# IODevices.net
KiCad netlist of a schematic drawn in Altium Designer
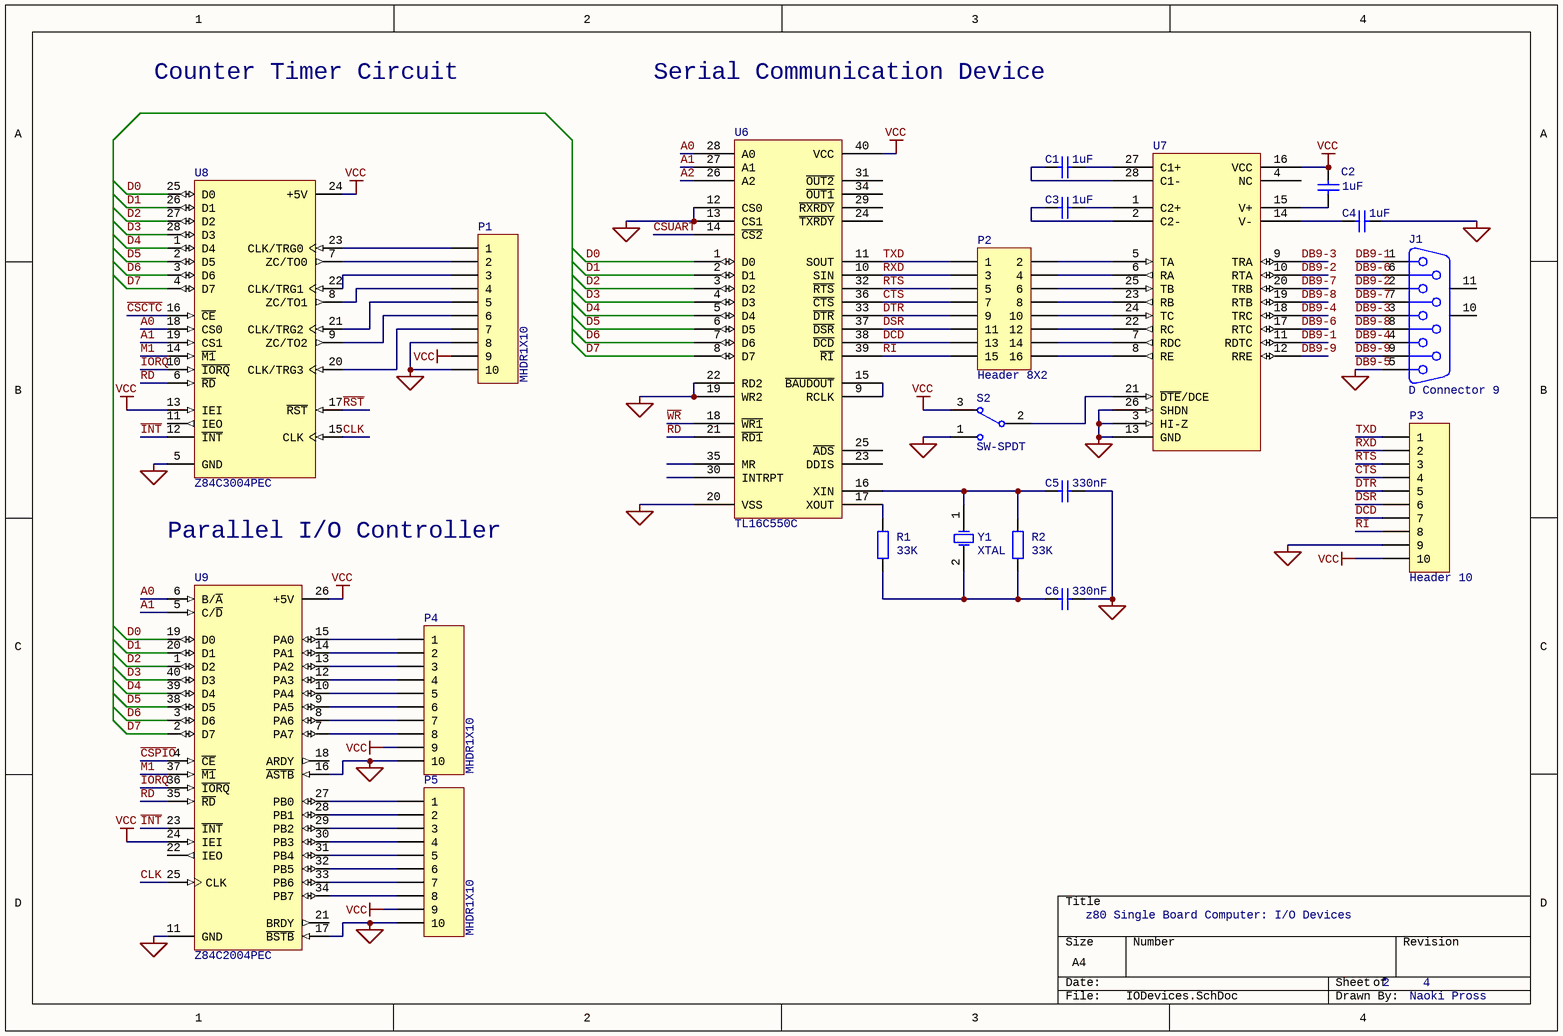
[diagram p0: IODevices.SchDoc]

(export (version "E")
  (design (tool "Eeschema 10.0.6"))
  (components
    (comp (ref "C1")
      (value "1uF")
      (footprint "RAD-0.3")
      (description "Capacitor")
      (fields (field (name "Comment") "Cap") (field (name "PUBLISHER") "Altium Limited"))
      (libsource (lib "z80uPC") (part "Cap"))
    )
    (comp (ref "C2")
      (value "1uF")
      (footprint "RAD-0.3")
      (description "Capacitor")
      (fields (field (name "Comment") "Cap") (field (name "PUBLISHER") "Altium Limited"))
      (libsource (lib "z80uPC") (part "Cap"))
    )
    (comp (ref "C3")
      (value "1uF")
      (footprint "RAD-0.3")
      (description "Capacitor")
      (fields (field (name "Comment") "Cap") (field (name "PUBLISHER") "Altium Limited"))
      (libsource (lib "z80uPC") (part "Cap"))
    )
    (comp (ref "C4")
      (value "1uF")
      (footprint "RAD-0.3")
      (description "Capacitor")
      (fields (field (name "Comment") "Cap") (field (name "PUBLISHER") "Altium Limited"))
      (libsource (lib "z80uPC") (part "Cap"))
    )
    (comp (ref "C5")
      (value "330nF")
      (footprint "RAD-0.3")
      (description "Capacitor")
      (fields (field (name "Comment") "Cap") (field (name "PUBLISHER") "Altium Limited"))
      (libsource (lib "z80uPC") (part "Cap"))
    )
    (comp (ref "C6")
      (value "330nF")
      (footprint "RAD-0.3")
      (description "Capacitor")
      (fields (field (name "Comment") "Cap") (field (name "PUBLISHER") "Altium Limited"))
      (libsource (lib "z80uPC") (part "Cap"))
    )
    (comp (ref "J1")
      (value "D Connector 9")
      (footprint "DSUB1.385-2H9")
      (description "Receptacle Assembly, 9 Position, Right Angle")
      (fields (field (name "PUBLISHER") "Altium Limited"))
      (libsource (lib "Miscellaneous Connectors") (part "D Connector 9"))
    )
    (comp (ref "P1")
      (value "MHDR1X10")
      (footprint "MHDR2X5")
      (description "Header, 10-Pin")
      (fields (field (name "PUBLISHER") "Altium Limited"))
      (libsource (lib "Miscellaneous Connectors") (part "MHDR1X10"))
    )
    (comp (ref "P2")
      (value "Header 8X2")
      (footprint "HDR2X8")
      (description "Header, 8-Pin, Dual row")
      (fields (field (name "PUBLISHER") "Altium Limited"))
      (libsource (lib "Miscellaneous Connectors") (part "Header 8X2"))
    )
    (comp (ref "P3")
      (value "Header 10")
      (footprint "MHDR2X5")
      (description "Header, 10-Pin")
      (fields (field (name "PUBLISHER") "Altium Limited"))
      (libsource (lib "Miscellaneous Connectors") (part "Header 10"))
    )
    (comp (ref "P4")
      (value "MHDR1X10")
      (footprint "MHDR2X5")
      (description "Header, 10-Pin")
      (fields (field (name "PUBLISHER") "Altium Limited"))
      (libsource (lib "Miscellaneous Connectors") (part "MHDR1X10"))
    )
    (comp (ref "P5")
      (value "MHDR1X10")
      (footprint "MHDR2X5")
      (description "Header, 10-Pin")
      (fields (field (name "PUBLISHER") "Altium Limited"))
      (libsource (lib "Miscellaneous Connectors") (part "MHDR1X10"))
    )
    (comp (ref "R1")
      (value "33K")
      (footprint "AXIAL-0.4")
      (description "Resistor")
      (fields (field (name "Comment") "Res2") (field (name "PUBLISHER") "Altium Limited"))
      (libsource (lib "z80uPC") (part "Res2"))
    )
    (comp (ref "R2")
      (value "33K")
      (footprint "AXIAL-0.4")
      (description "Resistor")
      (fields (field (name "Comment") "Res2") (field (name "PUBLISHER") "Altium Limited"))
      (libsource (lib "z80uPC") (part "Res2"))
    )
    (comp (ref "S2")
      (value "SW-SPDT")
      (footprint "TL36WW15050")
      (description "SPDT Subminiature Toggle Switch, Right Angle Mounting, Vertical Actuation")
      (fields (field (name "PUBLISHER") "Altium Limited"))
      (libsource (lib "Miscellaneous Devices") (part "SW-SPDT"))
    )
    (comp (ref "U6") (value "TL16C550C") (libsource (lib "z80uPC") (part "TL16C550C")))
    (comp (ref "U7") (value "MAX214") (libsource (lib "z80uPC") (part "MAX214")))
    (comp (ref "U8")
      (value "Z84C3004PEC")
      (footprint "PDIP28")
      (description "CMOS Four-Channel Counter/Timer Circuit")
      (fields (field (name "PUBLISHER") "Altium Limited"))
      (libsource (lib "Zilog Logic Counter") (part "Z84C3004PEC"))
    )
    (comp (ref "U9")
      (value "Z84C2004PEC")
      (footprint "PDIP40")
      (description "CMOS Parallel I/O Controller")
      (fields (field (name "PUBLISHER") "Altium Limited"))
      (libsource (lib "Zilog Peripheral Interface") (part "Z84C2004PEC"))
    )
    (comp (ref "Y1")
      (value "XTAL")
      (footprint "R38")
      (description "Crystal Oscillator")
      (fields (field (name "PUBLISHER") "Altium Limited"))
      (libsource (lib "Miscellaneous Devices") (part "XTAL"))
    )
  )
  (nets
    (net (code "1") (name "/A0") (class "Default")
      (node (ref "U6") (pin "28") (pinfunction "A0_28") (pintype "passive"))
      (node (ref "U8") (pin "18") (pinfunction "CS0_18") (pintype "input"))
      (node (ref "U9") (pin "6") (pinfunction "B/~{A}_6") (pintype "input"))
    )
    (net (code "2") (name "/A1") (class "Default")
      (node (ref "U6") (pin "27") (pinfunction "A1_27") (pintype "passive"))
      (node (ref "U8") (pin "19") (pinfunction "CS1_19") (pintype "input"))
      (node (ref "U9") (pin "5") (pinfunction "C/~{D}_5") (pintype "input"))
    )
    (net (code "3") (name "/A2") (class "Default")
      (node (ref "U6") (pin "26") (pinfunction "A2_26") (pintype "passive"))
    )
    (net (code "4") (name "/CLK") (class "Default")
      (node (ref "U8") (pin "15") (pinfunction "CLK_15") (pintype "input"))
      (node (ref "U9") (pin "25") (pinfunction "CLK_25") (pintype "input"))
    )
    (net (code "5") (name "/D0") (class "Default")
      (node (ref "U6") (pin "1") (pinfunction "D0_1") (pintype "bidirectional"))
      (node (ref "U8") (pin "25") (pinfunction "D0_25") (pintype "bidirectional"))
      (node (ref "U9") (pin "19") (pinfunction "D0_19") (pintype "bidirectional"))
    )
    (net (code "6") (name "/D1") (class "Default")
      (node (ref "U6") (pin "2") (pinfunction "D1_2") (pintype "bidirectional"))
      (node (ref "U8") (pin "26") (pinfunction "D1_26") (pintype "bidirectional"))
      (node (ref "U9") (pin "20") (pinfunction "D1_20") (pintype "bidirectional"))
    )
    (net (code "7") (name "/D2") (class "Default")
      (node (ref "U6") (pin "3") (pinfunction "D2_3") (pintype "bidirectional"))
      (node (ref "U8") (pin "27") (pinfunction "D2_27") (pintype "bidirectional"))
      (node (ref "U9") (pin "1") (pinfunction "D2_1") (pintype "bidirectional"))
    )
    (net (code "8") (name "/D3") (class "Default")
      (node (ref "U6") (pin "4") (pinfunction "D3_4") (pintype "bidirectional"))
      (node (ref "U8") (pin "28") (pinfunction "D3_28") (pintype "bidirectional"))
      (node (ref "U9") (pin "40") (pinfunction "D3_40") (pintype "bidirectional"))
    )
    (net (code "9") (name "/D4") (class "Default")
      (node (ref "U6") (pin "5") (pinfunction "D4_5") (pintype "bidirectional"))
      (node (ref "U8") (pin "1") (pinfunction "D4_1") (pintype "bidirectional"))
      (node (ref "U9") (pin "39") (pinfunction "D4_39") (pintype "bidirectional"))
    )
    (net (code "10") (name "/D5") (class "Default")
      (node (ref "U6") (pin "6") (pinfunction "D5_6") (pintype "bidirectional"))
      (node (ref "U8") (pin "2") (pinfunction "D5_2") (pintype "bidirectional"))
      (node (ref "U9") (pin "38") (pinfunction "D5_38") (pintype "bidirectional"))
    )
    (net (code "11") (name "/D6") (class "Default")
      (node (ref "U6") (pin "7") (pinfunction "D6_7") (pintype "bidirectional"))
      (node (ref "U8") (pin "3") (pinfunction "D6_3") (pintype "bidirectional"))
      (node (ref "U9") (pin "3") (pinfunction "D6_3") (pintype "bidirectional"))
    )
    (net (code "12") (name "/D7") (class "Default")
      (node (ref "U6") (pin "8") (pinfunction "D7_8") (pintype "bidirectional"))
      (node (ref "U8") (pin "4") (pinfunction "D7_4") (pintype "bidirectional"))
      (node (ref "U9") (pin "2") (pinfunction "D7_2") (pintype "bidirectional"))
    )
    (net (code "13") (name "/DB9-1") (class "Default")
      (node (ref "J1") (pin "1") (pinfunction "1_1") (pintype "passive"))
      (node (ref "U7") (pin "11") (pinfunction "RDTC_11") (pintype "bidirectional"))
    )
    (net (code "14") (name "/DB9-2") (class "Default")
      (node (ref "J1") (pin "2") (pinfunction "2_2") (pintype "passive"))
      (node (ref "U7") (pin "10") (pinfunction "RTA_10") (pintype "bidirectional"))
    )
    (net (code "15") (name "/DB9-3") (class "Default")
      (node (ref "J1") (pin "3") (pinfunction "3_3") (pintype "passive"))
      (node (ref "U7") (pin "9") (pinfunction "TRA_9") (pintype "bidirectional"))
    )
    (net (code "16") (name "/DB9-4") (class "Default")
      (node (ref "J1") (pin "4") (pinfunction "4_4") (pintype "passive"))
      (node (ref "U7") (pin "18") (pinfunction "TRC_18") (pintype "bidirectional"))
    )
    (net (code "17") (name "/DB9-6") (class "Default")
      (node (ref "J1") (pin "6") (pinfunction "6_6") (pintype "passive"))
      (node (ref "U7") (pin "17") (pinfunction "RTC_17") (pintype "bidirectional"))
    )
    (net (code "18") (name "/DB9-7") (class "Default")
      (node (ref "J1") (pin "7") (pinfunction "7_7") (pintype "passive"))
      (node (ref "U7") (pin "20") (pinfunction "TRB_20") (pintype "bidirectional"))
    )
    (net (code "19") (name "/DB9-8") (class "Default")
      (node (ref "J1") (pin "8") (pinfunction "8_8") (pintype "passive"))
      (node (ref "U7") (pin "19") (pinfunction "RTB_19") (pintype "bidirectional"))
    )
    (net (code "20") (name "/DB9-9") (class "Default")
      (node (ref "J1") (pin "9") (pinfunction "9_9") (pintype "passive"))
      (node (ref "U7") (pin "12") (pinfunction "RRE_12") (pintype "bidirectional"))
    )
    (net (code "21") (name "/RXD") (class "Default")
      (node (ref "P2") (pin "3") (pinfunction "3_3") (pintype "passive"))
      (node (ref "P3") (pin "2") (pinfunction "2_2") (pintype "passive"))
      (node (ref "U6") (pin "10") (pinfunction "SIN_10") (pintype "passive"))
    )
    (net (code "22") (name "/TXD") (class "Default")
      (node (ref "P2") (pin "1") (pinfunction "1_1") (pintype "passive"))
      (node (ref "P3") (pin "1") (pinfunction "1_1") (pintype "passive"))
      (node (ref "U6") (pin "11") (pinfunction "SOUT_11") (pintype "passive"))
    )
    (net (code "23") (name "/~{CSCTC}") (class "Default")
      (node (ref "U8") (pin "16") (pinfunction "~{CE}_16") (pintype "input"))
    )
    (net (code "24") (name "/~{CSPIO}") (class "Default")
      (node (ref "U9") (pin "4") (pinfunction "~{CE}_4") (pintype "input"))
    )
    (net (code "25") (name "/~{CSUART}") (class "Default")
      (node (ref "U6") (pin "14") (pinfunction "~{CS2}_14") (pintype "passive"))
    )
    (net (code "26") (name "/~{CTS}") (class "Default")
      (node (ref "P2") (pin "7") (pinfunction "7_7") (pintype "passive"))
      (node (ref "P3") (pin "4") (pinfunction "4_4") (pintype "passive"))
      (node (ref "U6") (pin "36") (pinfunction "~{CTS}_36") (pintype "passive"))
    )
    (net (code "27") (name "/~{DCD}") (class "Default")
      (node (ref "P2") (pin "13") (pinfunction "13_13") (pintype "passive"))
      (node (ref "P3") (pin "7") (pinfunction "7_7") (pintype "passive"))
      (node (ref "U6") (pin "38") (pinfunction "~{DCD}_38") (pintype "passive"))
    )
    (net (code "28") (name "/~{DSR}") (class "Default")
      (node (ref "P2") (pin "11") (pinfunction "11_11") (pintype "passive"))
      (node (ref "P3") (pin "6") (pinfunction "6_6") (pintype "passive"))
      (node (ref "U6") (pin "37") (pinfunction "~{DSR}_37") (pintype "passive"))
    )
    (net (code "29") (name "/~{DTR}") (class "Default")
      (node (ref "P2") (pin "9") (pinfunction "9_9") (pintype "passive"))
      (node (ref "P3") (pin "5") (pinfunction "5_5") (pintype "passive"))
      (node (ref "U6") (pin "33") (pinfunction "~{DTR}_33") (pintype "passive"))
    )
    (net (code "30") (name "/~{INT}") (class "Default")
      (node (ref "U8") (pin "12") (pinfunction "~{INT}_12") (pintype "open_collector"))
      (node (ref "U9") (pin "23") (pinfunction "~{INT}_23") (pintype "open_collector"))
    )
    (net (code "31") (name "/~{IORQ}") (class "Default")
      (node (ref "U8") (pin "10") (pinfunction "~{IORQ}_10") (pintype "input"))
      (node (ref "U9") (pin "36") (pinfunction "~{IORQ}_36") (pintype "input"))
    )
    (net (code "32") (name "/~{M1}") (class "Default")
      (node (ref "U8") (pin "14") (pinfunction "~{M1}_14") (pintype "input"))
      (node (ref "U9") (pin "37") (pinfunction "~{M1}_37") (pintype "input"))
    )
    (net (code "33") (name "/~{RD}") (class "Default")
      (node (ref "U6") (pin "21") (pinfunction "~{RD1}_21") (pintype "passive"))
      (node (ref "U8") (pin "6") (pinfunction "~{RD}_6") (pintype "input"))
      (node (ref "U9") (pin "35") (pinfunction "~{RD}_35") (pintype "input"))
    )
    (net (code "34") (name "/~{RI}") (class "Default")
      (node (ref "P2") (pin "15") (pinfunction "15_15") (pintype "passive"))
      (node (ref "P3") (pin "8") (pinfunction "8_8") (pintype "passive"))
      (node (ref "U6") (pin "39") (pinfunction "~{RI}_39") (pintype "passive"))
    )
    (net (code "35") (name "/~{RST}") (class "Default")
      (node (ref "U8") (pin "17") (pinfunction "~{RST}_17") (pintype "input"))
    )
    (net (code "36") (name "/~{RTS}") (class "Default")
      (node (ref "P2") (pin "5") (pinfunction "5_5") (pintype "passive"))
      (node (ref "P3") (pin "3") (pinfunction "3_3") (pintype "passive"))
      (node (ref "U6") (pin "32") (pinfunction "~{RTS}_32") (pintype "passive"))
    )
    (net (code "37") (name "/~{WR}") (class "Default")
      (node (ref "U6") (pin "18") (pinfunction "~{WR1}_18") (pintype "passive"))
    )
    (net (code "38") (name "GND") (class "Default")
      (node (ref "C4") (pin "2") (pinfunction "2_2") (pintype "passive"))
      (node (ref "C5") (pin "2") (pinfunction "2_2") (pintype "passive"))
      (node (ref "C6") (pin "2") (pinfunction "2_2") (pintype "passive"))
      (node (ref "J1") (pin "5") (pinfunction "5_5") (pintype "passive"))
      (node (ref "P1") (pin "10") (pinfunction "10_10") (pintype "passive"))
      (node (ref "P1") (pin "8") (pinfunction "8_8") (pintype "passive"))
      (node (ref "P3") (pin "9") (pinfunction "9_9") (pintype "passive"))
      (node (ref "P4") (pin "10") (pinfunction "10_10") (pintype "passive"))
      (node (ref "P5") (pin "10") (pinfunction "10_10") (pintype "passive"))
      (node (ref "S2") (pin "1") (pinfunction "1_1") (pintype "passive"))
      (node (ref "U6") (pin "12") (pinfunction "CS0_12") (pintype "passive"))
      (node (ref "U6") (pin "13") (pinfunction "CS1_13") (pintype "passive"))
      (node (ref "U6") (pin "19") (pinfunction "WR2_19") (pintype "passive"))
      (node (ref "U6") (pin "20") (pinfunction "VSS_20") (pintype "power_in"))
      (node (ref "U6") (pin "22") (pinfunction "RD2_22") (pintype "passive"))
      (node (ref "U7") (pin "13") (pinfunction "GND_13") (pintype "passive"))
      (node (ref "U7") (pin "26") (pinfunction "SHDN_26") (pintype "input"))
      (node (ref "U7") (pin "3") (pinfunction "HI-Z_3") (pintype "input"))
      (node (ref "U8") (pin "5") (pinfunction "GND_5") (pintype "power_in"))
      (node (ref "U9") (pin "11") (pinfunction "GND_11") (pintype "power_in"))
      (node (ref "U9") (pin "16") (pinfunction "~{ASTB}_16") (pintype "input"))
      (node (ref "U9") (pin "17") (pinfunction "~{BSTB}_17") (pintype "input"))
    )
    (net (code "39") (name "Net-(U6-RCLK)") (class "Default")
      (node (ref "U6") (pin "15") (pinfunction "~{BAUDOUT}_15") (pintype "passive"))
      (node (ref "U6") (pin "9") (pinfunction "RCLK_9") (pintype "passive"))
    )
    (net (code "40") (name "Net-(U6-XIN)") (class "Default")
      (node (ref "C5") (pin "1") (pinfunction "1_1") (pintype "passive"))
      (node (ref "R2") (pin "2") (pinfunction "2_2") (pintype "passive"))
      (node (ref "U6") (pin "16") (pinfunction "XIN_16") (pintype "passive"))
      (node (ref "Y1") (pin "1") (pinfunction "OSC1_1") (pintype "passive"))
    )
    (net (code "41") (name "Net-(U6-XOUT)") (class "Default")
      (node (ref "R1") (pin "2") (pinfunction "2_2") (pintype "passive"))
      (node (ref "U6") (pin "17") (pinfunction "XOUT_17") (pintype "passive"))
    )
    (net (code "42") (name "Net-(U7-C1+)") (class "Default")
      (node (ref "C1") (pin "2") (pinfunction "2_2") (pintype "passive"))
      (node (ref "U7") (pin "27") (pinfunction "C1+_27") (pintype "passive"))
    )
    (net (code "43") (name "Net-(U7-C1-)") (class "Default")
      (node (ref "C1") (pin "1") (pinfunction "1_1") (pintype "passive"))
      (node (ref "U7") (pin "28") (pinfunction "C1-_28") (pintype "passive"))
    )
    (net (code "44") (name "Net-(U7-C2+)") (class "Default")
      (node (ref "C3") (pin "2") (pinfunction "2_2") (pintype "passive"))
      (node (ref "U7") (pin "1") (pinfunction "C2+_1") (pintype "passive"))
    )
    (net (code "45") (name "Net-(U7-C2-)") (class "Default")
      (node (ref "C3") (pin "1") (pinfunction "1_1") (pintype "passive"))
      (node (ref "U7") (pin "2") (pinfunction "C2-_2") (pintype "passive"))
    )
    (net (code "46") (name "Net-(U7-RA)") (class "Default")
      (node (ref "P2") (pin "4") (pinfunction "4_4") (pintype "passive"))
      (node (ref "U7") (pin "6") (pinfunction "RA_6") (pintype "output"))
    )
    (net (code "47") (name "Net-(U7-RB)") (class "Default")
      (node (ref "P2") (pin "8") (pinfunction "8_8") (pintype "passive"))
      (node (ref "U7") (pin "23") (pinfunction "RB_23") (pintype "output"))
    )
    (net (code "48") (name "Net-(U7-RC)") (class "Default")
      (node (ref "P2") (pin "12") (pinfunction "12_12") (pintype "passive"))
      (node (ref "U7") (pin "22") (pinfunction "RC_22") (pintype "output"))
    )
    (net (code "49") (name "Net-(U7-RDC)") (class "Default")
      (node (ref "P2") (pin "14") (pinfunction "14_14") (pintype "passive"))
      (node (ref "U7") (pin "7") (pinfunction "RDC_7") (pintype "output"))
    )
    (net (code "50") (name "Net-(U7-RE)") (class "Default")
      (node (ref "P2") (pin "16") (pinfunction "16_16") (pintype "passive"))
      (node (ref "U7") (pin "8") (pinfunction "RE_8") (pintype "output"))
    )
    (net (code "51") (name "Net-(U7-TA)") (class "Default")
      (node (ref "P2") (pin "2") (pinfunction "2_2") (pintype "passive"))
      (node (ref "U7") (pin "5") (pinfunction "TA_5") (pintype "input"))
    )
    (net (code "52") (name "Net-(U7-TB)") (class "Default")
      (node (ref "P2") (pin "6") (pinfunction "6_6") (pintype "passive"))
      (node (ref "U7") (pin "25") (pinfunction "TB_25") (pintype "input"))
    )
    (net (code "53") (name "Net-(U7-TC)") (class "Default")
      (node (ref "P2") (pin "10") (pinfunction "10_10") (pintype "passive"))
      (node (ref "U7") (pin "24") (pinfunction "TC_24") (pintype "input"))
    )
    (net (code "54") (name "Net-(U7-V+)") (class "Default")
      (node (ref "C2") (pin "1") (pinfunction "1_1") (pintype "passive"))
      (node (ref "U7") (pin "15") (pinfunction "V+_15") (pintype "passive"))
    )
    (net (code "55") (name "Net-(U7-V-)") (class "Default")
      (node (ref "C4") (pin "1") (pinfunction "1_1") (pintype "passive"))
      (node (ref "U7") (pin "14") (pinfunction "V-_14") (pintype "passive"))
    )
    (net (code "56") (name "Net-(U7-~{DTE}{slash}DCE)") (class "Default")
      (node (ref "S2") (pin "2") (pinfunction "2_2") (pintype "passive"))
      (node (ref "U7") (pin "21") (pinfunction "~{DTE}/DCE_21") (pintype "input"))
    )
    (net (code "57") (name "Net-(U8-CLK{slash}TRG0)") (class "Default")
      (node (ref "P1") (pin "1") (pinfunction "1_1") (pintype "passive"))
      (node (ref "U8") (pin "23") (pinfunction "CLK/TRG0_23") (pintype "input"))
    )
    (net (code "58") (name "Net-(U8-CLK{slash}TRG1)") (class "Default")
      (node (ref "P1") (pin "3") (pinfunction "3_3") (pintype "passive"))
      (node (ref "U8") (pin "22") (pinfunction "CLK/TRG1_22") (pintype "input"))
    )
    (net (code "59") (name "Net-(U8-CLK{slash}TRG2)") (class "Default")
      (node (ref "P1") (pin "5") (pinfunction "5_5") (pintype "passive"))
      (node (ref "U8") (pin "21") (pinfunction "CLK/TRG2_21") (pintype "input"))
    )
    (net (code "60") (name "Net-(U8-CLK{slash}TRG3)") (class "Default")
      (node (ref "P1") (pin "7") (pinfunction "7_7") (pintype "passive"))
      (node (ref "U8") (pin "20") (pinfunction "CLK/TRG3_20") (pintype "input"))
    )
    (net (code "61") (name "Net-(U8-ZC{slash}TO0)") (class "Default")
      (node (ref "P1") (pin "2") (pinfunction "2_2") (pintype "passive"))
      (node (ref "U8") (pin "7") (pinfunction "ZC/TO0_7") (pintype "output"))
    )
    (net (code "62") (name "Net-(U8-ZC{slash}TO1)") (class "Default")
      (node (ref "P1") (pin "4") (pinfunction "4_4") (pintype "passive"))
      (node (ref "U8") (pin "8") (pinfunction "ZC/TO1_8") (pintype "output"))
    )
    (net (code "63") (name "Net-(U8-ZC{slash}TO2)") (class "Default")
      (node (ref "P1") (pin "6") (pinfunction "6_6") (pintype "passive"))
      (node (ref "U8") (pin "9") (pinfunction "ZC/TO2_9") (pintype "output"))
    )
    (net (code "64") (name "Net-(U9-PA0)") (class "Default")
      (node (ref "P4") (pin "1") (pinfunction "1_1") (pintype "passive"))
      (node (ref "U9") (pin "15") (pinfunction "PA0_15") (pintype "bidirectional"))
    )
    (net (code "65") (name "Net-(U9-PA1)") (class "Default")
      (node (ref "P4") (pin "2") (pinfunction "2_2") (pintype "passive"))
      (node (ref "U9") (pin "14") (pinfunction "PA1_14") (pintype "bidirectional"))
    )
    (net (code "66") (name "Net-(U9-PA2)") (class "Default")
      (node (ref "P4") (pin "3") (pinfunction "3_3") (pintype "passive"))
      (node (ref "U9") (pin "13") (pinfunction "PA2_13") (pintype "bidirectional"))
    )
    (net (code "67") (name "Net-(U9-PA3)") (class "Default")
      (node (ref "P4") (pin "4") (pinfunction "4_4") (pintype "passive"))
      (node (ref "U9") (pin "12") (pinfunction "PA3_12") (pintype "bidirectional"))
    )
    (net (code "68") (name "Net-(U9-PA4)") (class "Default")
      (node (ref "P4") (pin "5") (pinfunction "5_5") (pintype "passive"))
      (node (ref "U9") (pin "10") (pinfunction "PA4_10") (pintype "bidirectional"))
    )
    (net (code "69") (name "Net-(U9-PA5)") (class "Default")
      (node (ref "P4") (pin "6") (pinfunction "6_6") (pintype "passive"))
      (node (ref "U9") (pin "9") (pinfunction "PA5_9") (pintype "bidirectional"))
    )
    (net (code "70") (name "Net-(U9-PA6)") (class "Default")
      (node (ref "P4") (pin "7") (pinfunction "7_7") (pintype "passive"))
      (node (ref "U9") (pin "8") (pinfunction "PA6_8") (pintype "bidirectional"))
    )
    (net (code "71") (name "Net-(U9-PA7)") (class "Default")
      (node (ref "P4") (pin "8") (pinfunction "8_8") (pintype "passive"))
      (node (ref "U9") (pin "7") (pinfunction "PA7_7") (pintype "bidirectional"))
    )
    (net (code "72") (name "Net-(U9-PB0)") (class "Default")
      (node (ref "P5") (pin "1") (pinfunction "1_1") (pintype "passive"))
      (node (ref "U9") (pin "27") (pinfunction "PB0_27") (pintype "bidirectional"))
    )
    (net (code "73") (name "Net-(U9-PB1)") (class "Default")
      (node (ref "P5") (pin "2") (pinfunction "2_2") (pintype "passive"))
      (node (ref "U9") (pin "28") (pinfunction "PB1_28") (pintype "bidirectional"))
    )
    (net (code "74") (name "Net-(U9-PB2)") (class "Default")
      (node (ref "P5") (pin "3") (pinfunction "3_3") (pintype "passive"))
      (node (ref "U9") (pin "29") (pinfunction "PB2_29") (pintype "bidirectional"))
    )
    (net (code "75") (name "Net-(U9-PB3)") (class "Default")
      (node (ref "P5") (pin "4") (pinfunction "4_4") (pintype "passive"))
      (node (ref "U9") (pin "30") (pinfunction "PB3_30") (pintype "bidirectional"))
    )
    (net (code "76") (name "Net-(U9-PB4)") (class "Default")
      (node (ref "P5") (pin "5") (pinfunction "5_5") (pintype "passive"))
      (node (ref "U9") (pin "31") (pinfunction "PB4_31") (pintype "bidirectional"))
    )
    (net (code "77") (name "Net-(U9-PB5)") (class "Default")
      (node (ref "P5") (pin "6") (pinfunction "6_6") (pintype "passive"))
      (node (ref "U9") (pin "32") (pinfunction "PB5_32") (pintype "bidirectional"))
    )
    (net (code "78") (name "Net-(U9-PB6)") (class "Default")
      (node (ref "P5") (pin "7") (pinfunction "7_7") (pintype "passive"))
      (node (ref "U9") (pin "33") (pinfunction "PB6_33") (pintype "bidirectional"))
    )
    (net (code "79") (name "Net-(U9-PB7)") (class "Default")
      (node (ref "P5") (pin "8") (pinfunction "8_8") (pintype "passive"))
      (node (ref "U9") (pin "34") (pinfunction "PB7_34") (pintype "bidirectional"))
    )
    (net (code "80") (name "Net-(Y1-OSC2)") (class "Default")
      (node (ref "C6") (pin "1") (pinfunction "1_1") (pintype "passive"))
      (node (ref "R1") (pin "1") (pinfunction "1_1") (pintype "passive"))
      (node (ref "R2") (pin "1") (pinfunction "1_1") (pintype "passive"))
      (node (ref "Y1") (pin "2") (pinfunction "OSC2_2") (pintype "passive"))
    )
    (net (code "81") (name "VCC") (class "Default")
      (node (ref "C2") (pin "2") (pinfunction "2_2") (pintype "passive"))
      (node (ref "P1") (pin "9") (pinfunction "9_9") (pintype "passive"))
      (node (ref "P3") (pin "10") (pinfunction "10_10") (pintype "passive"))
      (node (ref "P4") (pin "9") (pinfunction "9_9") (pintype "passive"))
      (node (ref "P5") (pin "9") (pinfunction "9_9") (pintype "passive"))
      (node (ref "S2") (pin "3") (pinfunction "3_3") (pintype "passive"))
      (node (ref "U6") (pin "40") (pinfunction "VCC_40") (pintype "passive"))
      (node (ref "U7") (pin "16") (pinfunction "VCC_16") (pintype "passive"))
      (node (ref "U8") (pin "13") (pinfunction "IEI_13") (pintype "input"))
      (node (ref "U8") (pin "24") (pinfunction "+5V_24") (pintype "power_in"))
      (node (ref "U9") (pin "24") (pinfunction "IEI_24") (pintype "input"))
      (node (ref "U9") (pin "26") (pinfunction "+5V_26") (pintype "power_in"))
    )
    (net (code "82") (name "unconnected-(J1-MH1-Pad10)") (class "Default")
      (node (ref "J1") (pin "10") (pinfunction "MH1_10") (pintype "passive"))
    )
    (net (code "83") (name "unconnected-(J1-MH2-Pad11)") (class "Default")
      (node (ref "J1") (pin "11") (pinfunction "MH2_11") (pintype "passive"))
    )
    (net (code "84") (name "unconnected-(U6-DDIS-Pad23)") (class "Default")
      (node (ref "U6") (pin "23") (pinfunction "DDIS_23") (pintype "passive"))
    )
    (net (code "85") (name "unconnected-(U6-INTRPT-Pad30)") (class "Default")
      (node (ref "U6") (pin "30") (pinfunction "INTRPT_30") (pintype "passive"))
    )
    (net (code "86") (name "unconnected-(U6-MR-Pad35)") (class "Default")
      (node (ref "U6") (pin "35") (pinfunction "MR_35") (pintype "passive"))
    )
    (net (code "87") (name "unconnected-(U6-~{ADS}-Pad25)") (class "Default")
      (node (ref "U6") (pin "25") (pinfunction "~{ADS}_25") (pintype "passive"))
    )
    (net (code "88") (name "unconnected-(U6-~{OUT1}-Pad34)") (class "Default")
      (node (ref "U6") (pin "34") (pinfunction "~{OUT1}_34") (pintype "passive"))
    )
    (net (code "89") (name "unconnected-(U6-~{OUT2}-Pad31)") (class "Default")
      (node (ref "U6") (pin "31") (pinfunction "~{OUT2}_31") (pintype "passive"))
    )
    (net (code "90") (name "unconnected-(U6-~{RXRDY}-Pad29)") (class "Default")
      (node (ref "U6") (pin "29") (pinfunction "~{RXRDY}_29") (pintype "passive"))
    )
    (net (code "91") (name "unconnected-(U6-~{TXRDY}-Pad24)") (class "Default")
      (node (ref "U6") (pin "24") (pinfunction "~{TXRDY}_24") (pintype "passive"))
    )
    (net (code "92") (name "unconnected-(U7-NC-Pad4)") (class "Default")
      (node (ref "U7") (pin "4") (pinfunction "NC_4") (pintype "passive"))
    )
    (net (code "93") (name "unconnected-(U8-IEO-Pad11)") (class "Default")
      (node (ref "U8") (pin "11") (pinfunction "IEO_11") (pintype "output"))
    )
    (net (code "94") (name "unconnected-(U9-ARDY-Pad18)") (class "Default")
      (node (ref "U9") (pin "18") (pinfunction "ARDY_18") (pintype "output"))
    )
    (net (code "95") (name "unconnected-(U9-BRDY-Pad21)") (class "Default")
      (node (ref "U9") (pin "21") (pinfunction "BRDY_21") (pintype "output"))
    )
    (net (code "96") (name "unconnected-(U9-IEO-Pad22)") (class "Default")
      (node (ref "U9") (pin "22") (pinfunction "IEO_22") (pintype "output"))
    )
  )
)
